# opengarden_v1.net
KiCad netlist of a schematic drawn in EAGLE
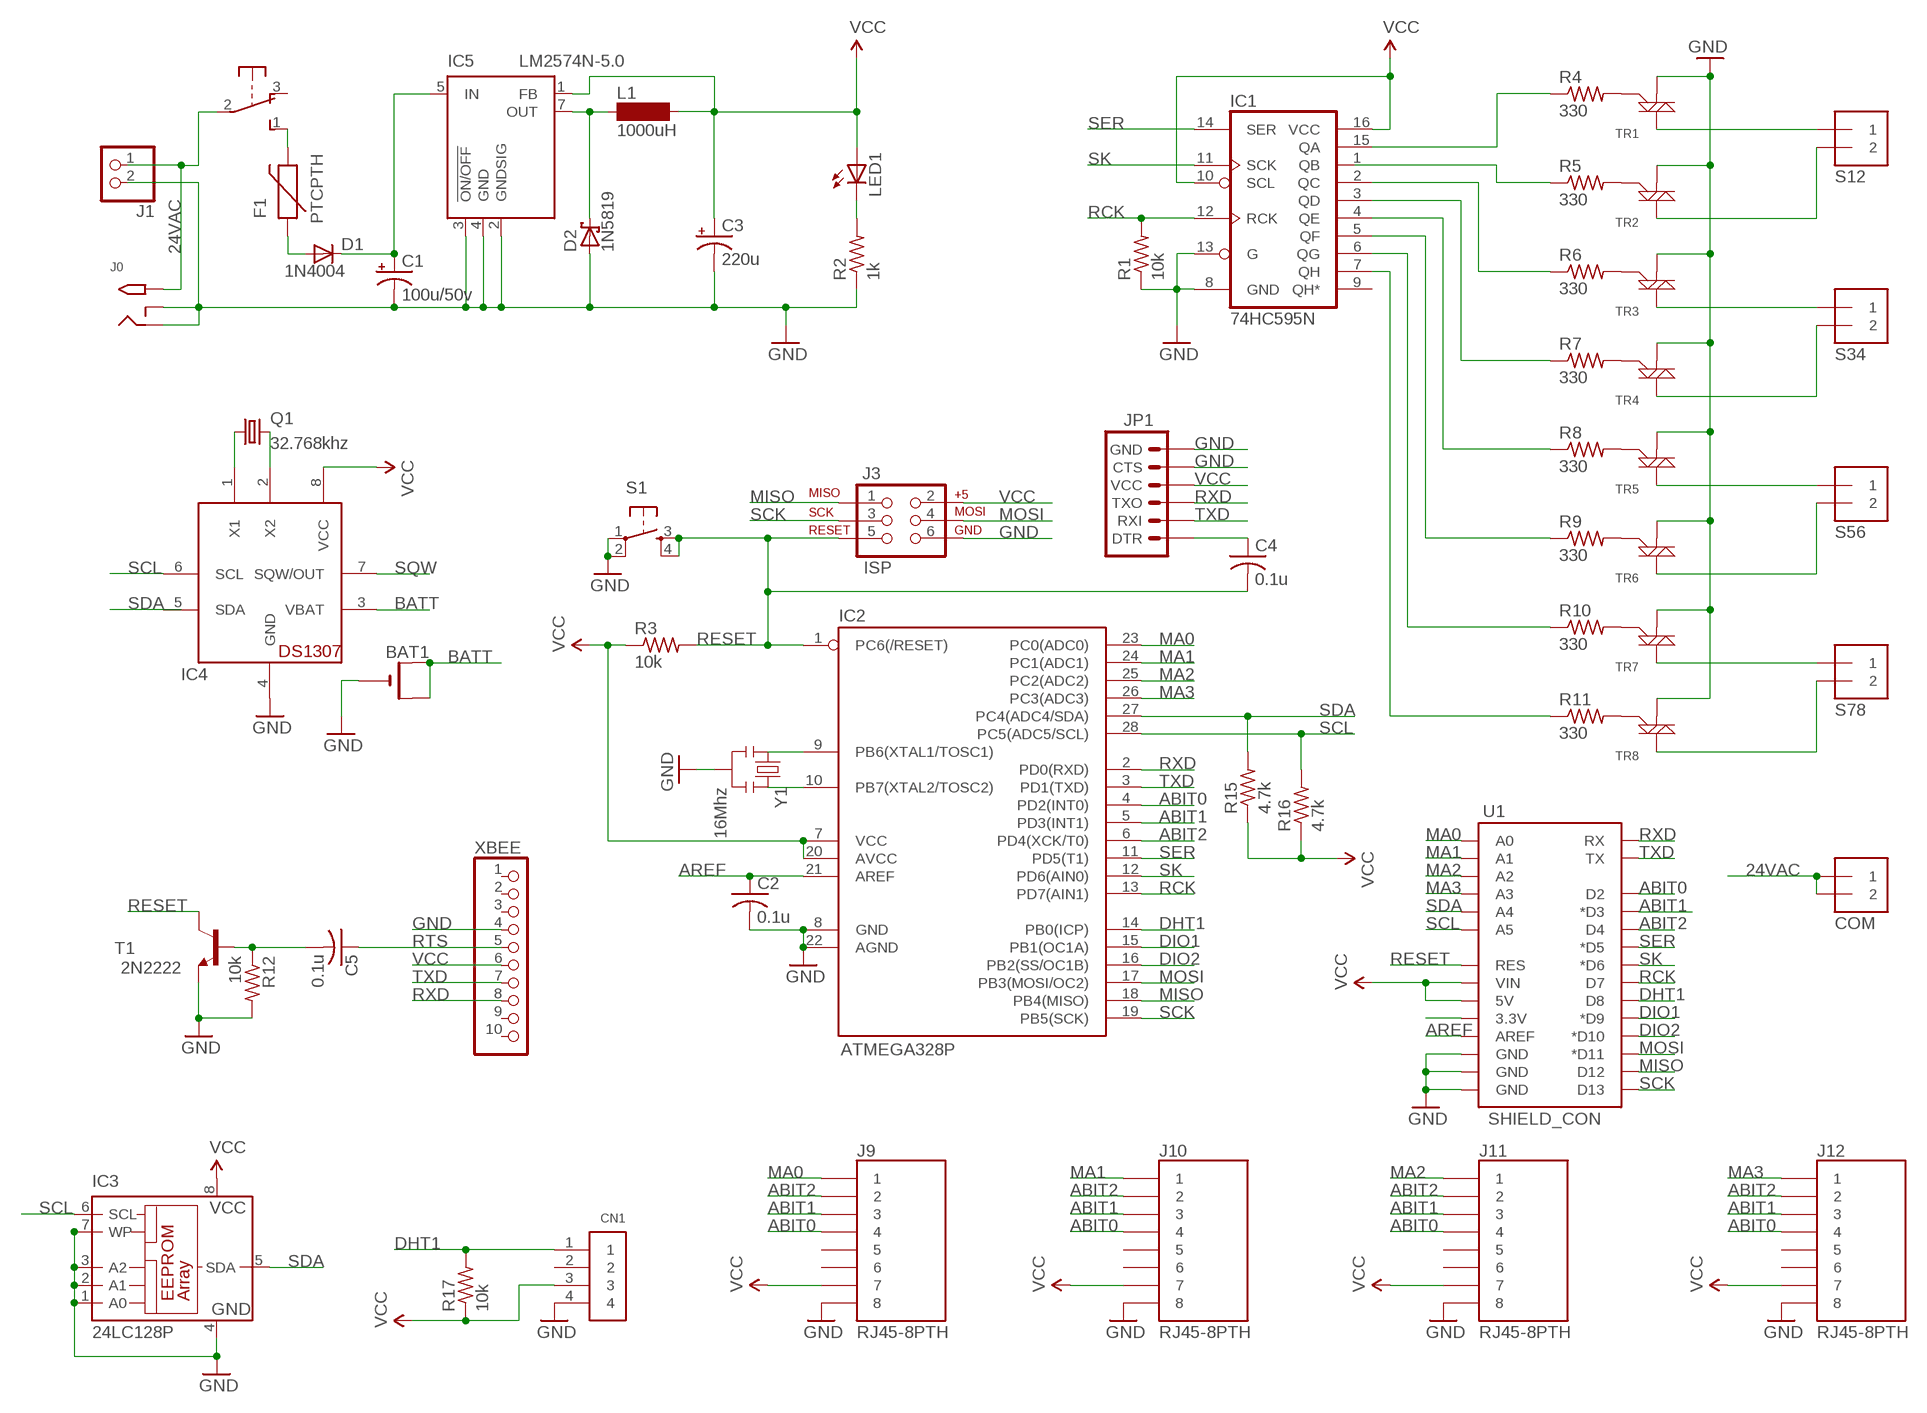
[diagram p0: schematic, sheet 1]

(export (version "E")
  (design (tool "Eeschema 10.0.6"))
  (components
    (comp (ref "BAT1")
      (value "CR1220THM")
      (footprint "eagle-import:CR1220-THM")
      (libsource (lib "eagle-import") (part "CR1220THM"))
    )
    (comp (ref "C1")
      (value "100u/50v")
      (footprint "eagle-import:E3,5-8")
      (libsource (lib "eagle-import") (part "CPOL-USE3.5-8"))
    )
    (comp (ref "C2")
      (value "0.1u")
      (footprint "eagle-import:C025-024X044")
      (libsource (lib "eagle-import") (part "C-US025-024X044"))
    )
    (comp (ref "C3")
      (value "220u")
      (footprint "eagle-import:E2,5-6E")
      (libsource (lib "eagle-import") (part "CPOL-USE2,5-6E"))
    )
    (comp (ref "C4")
      (value "0.1u")
      (footprint "eagle-import:C025-024X044")
      (libsource (lib "eagle-import") (part "C-US025-024X044"))
    )
    (comp (ref "C5")
      (value "0.1u")
      (footprint "eagle-import:C025-024X044")
      (libsource (lib "eagle-import") (part "C-US025-024X044"))
    )
    (comp (ref "CN1")
      (value "1X4-3.5MM")
      (footprint "eagle-import:1X04-3.5MM")
      (libsource (lib "eagle-import") (part "1X4-3.5MM"))
    )
    (comp (ref "COM")
      (value "1X2-3.5MM")
      (footprint "eagle-import:1X2-3.5MM")
      (libsource (lib "eagle-import") (part "1X2-3.5MM"))
    )
    (comp (ref "D1")
      (value "1N4004")
      (footprint "eagle-import:DO41-10")
      (libsource (lib "eagle-import") (part "1N4004"))
    )
    (comp (ref "D2")
      (value "1N5819")
      (footprint "eagle-import:DO41-10")
      (libsource (lib "eagle-import") (part "SCHOTTKY-DIODEDO41"))
    )
    (comp (ref "F1")
      (value "PTCPTH")
      (footprint "eagle-import:PTC")
      (libsource (lib "eagle-import") (part "PTCPTH"))
    )
    (comp (ref "IC1")
      (value "74HC595N")
      (footprint "eagle-import:DIL16")
      (libsource (lib "eagle-import") (part "74595NLS"))
    )
    (comp (ref "IC2")
      (value "ATMEGA328P")
      (footprint "eagle-import:DIL28-3")
      (libsource (lib "eagle-import") (part "AVR-MEGA8-PPTH"))
    )
    (comp (ref "IC3")
      (value "24LC128P")
      (footprint "eagle-import:DIL8")
      (fields (field (name "MF") "MICROCHIP") (field (name "MPN") "24LC128-I/P"))
      (libsource (lib "eagle-import") (part "24PLC128"))
    )
    (comp (ref "IC4")
      (value "DS1307")
      (footprint "eagle-import:DIL08")
      (libsource (lib "eagle-import") (part "DS1307"))
    )
    (comp (ref "IC5")
      (value "LM2574N-5.0")
      (footprint "eagle-import:DIL08")
      (libsource (lib "eagle-import") (part "LM2574?-N5.0"))
    )
    (comp (ref "J0")
      (value "2.1MMJACKTHM")
      (footprint "eagle-import:PJ-102A")
      (libsource (lib "eagle-import") (part "2.1MMJACKTHM"))
    )
    (comp (ref "J1")
      (value "JST_2PIN-THM")
      (footprint "eagle-import:JST-PH-2-THM")
      (libsource (lib "eagle-import") (part "JST_2PIN-THM"))
    )
    (comp (ref "J2")
      (value "OS102011MA1Q")
      (footprint "eagle-import:OS102011MA1Q")
      (libsource (lib "eagle-import") (part "OS102011MA1Q"))
    )
    (comp (ref "J3")
      (value "ISP")
      (footprint "eagle-import:2X3")
      (libsource (lib "eagle-import") (part "AVR_SPI_PRG_6PTH"))
    )
    (comp (ref "J9")
      (value "RJ45-8PTH")
      (footprint "eagle-import:RJ45-8")
      (libsource (lib "eagle-import") (part "RJ45-8PTH"))
    )
    (comp (ref "J10")
      (value "RJ45-8PTH")
      (footprint "eagle-import:RJ45-8")
      (libsource (lib "eagle-import") (part "RJ45-8PTH"))
    )
    (comp (ref "J11")
      (value "RJ45-8PTH")
      (footprint "eagle-import:RJ45-8")
      (libsource (lib "eagle-import") (part "RJ45-8PTH"))
    )
    (comp (ref "J12")
      (value "RJ45-8PTH")
      (footprint "eagle-import:RJ45-8")
      (libsource (lib "eagle-import") (part "RJ45-8PTH"))
    )
    (comp (ref "JP1")
      (value "ARDUINO_SERIAL_PROGRAMLOCK")
      (footprint "eagle-import:1X06_LOCK")
      (libsource (lib "eagle-import") (part "ARDUINO_SERIAL_PROGRAMLOCK"))
    )
    (comp (ref "L1")
      (value "1000uH")
      (footprint "eagle-import:BS11")
      (libsource (lib "eagle-import") (part "BS11"))
    )
    (comp (ref "LED1")
      (value "LED3MM")
      (footprint "eagle-import:LED3MM")
      (libsource (lib "eagle-import") (part "LED3MM"))
    )
    (comp (ref "Q1")
      (value "32.768khz")
      (footprint "eagle-import:TC26V")
      (libsource (lib "eagle-import") (part "CRYSTALTC26V"))
    )
    (comp (ref "R1")
      (value "10k")
      (footprint "eagle-import:0204_7")
      (libsource (lib "eagle-import") (part "R-US_0204/7"))
    )
    (comp (ref "R2")
      (value "1k")
      (footprint "eagle-import:0204_7")
      (libsource (lib "eagle-import") (part "R-US_0204/7"))
    )
    (comp (ref "R3")
      (value "10k")
      (footprint "eagle-import:0204_7")
      (libsource (lib "eagle-import") (part "R-US_0204/7"))
    )
    (comp (ref "R4")
      (value "330")
      (footprint "eagle-import:0204_7")
      (libsource (lib "eagle-import") (part "R-US_0204/7"))
    )
    (comp (ref "R5")
      (value "330")
      (footprint "eagle-import:0204_7")
      (libsource (lib "eagle-import") (part "R-US_0204/7"))
    )
    (comp (ref "R6")
      (value "330")
      (footprint "eagle-import:0204_7")
      (libsource (lib "eagle-import") (part "R-US_0204/7"))
    )
    (comp (ref "R7")
      (value "330")
      (footprint "eagle-import:0204_7")
      (libsource (lib "eagle-import") (part "R-US_0204/7"))
    )
    (comp (ref "R8")
      (value "330")
      (footprint "eagle-import:0204_7")
      (libsource (lib "eagle-import") (part "R-US_0204/7"))
    )
    (comp (ref "R9")
      (value "330")
      (footprint "eagle-import:0204_7")
      (libsource (lib "eagle-import") (part "R-US_0204/7"))
    )
    (comp (ref "R10")
      (value "330")
      (footprint "eagle-import:0204_7")
      (libsource (lib "eagle-import") (part "R-US_0204/7"))
    )
    (comp (ref "R11")
      (value "330")
      (footprint "eagle-import:0204_7")
      (libsource (lib "eagle-import") (part "R-US_0204/7"))
    )
    (comp (ref "R12")
      (value "10k")
      (footprint "eagle-import:0204_7")
      (libsource (lib "eagle-import") (part "R-US_0204/7"))
    )
    (comp (ref "R15")
      (value "4.7k")
      (footprint "eagle-import:0204_7")
      (libsource (lib "eagle-import") (part "R-US_0204/7"))
    )
    (comp (ref "R16")
      (value "4.7k")
      (footprint "eagle-import:0204_7")
      (libsource (lib "eagle-import") (part "R-US_0204/7"))
    )
    (comp (ref "R17")
      (value "10k")
      (footprint "eagle-import:0204_7")
      (libsource (lib "eagle-import") (part "R-US_0204/7"))
    )
    (comp (ref "S1")
      (value "TAC_SWITCHPTH")
      (footprint "eagle-import:TACTILE-PTH")
      (libsource (lib "eagle-import") (part "TAC_SWITCHPTH"))
    )
    (comp (ref "S12")
      (value "1X2-3.5MM")
      (footprint "eagle-import:1X2-3.5MM")
      (libsource (lib "eagle-import") (part "1X2-3.5MM"))
    )
    (comp (ref "S34")
      (value "1X2-3.5MM")
      (footprint "eagle-import:1X2-3.5MM")
      (libsource (lib "eagle-import") (part "1X2-3.5MM"))
    )
    (comp (ref "S56")
      (value "1X2-3.5MM")
      (footprint "eagle-import:1X2-3.5MM")
      (libsource (lib "eagle-import") (part "1X2-3.5MM"))
    )
    (comp (ref "S78")
      (value "1X2-3.5MM")
      (footprint "eagle-import:1X2-3.5MM")
      (libsource (lib "eagle-import") (part "1X2-3.5MM"))
    )
    (comp (ref "T1")
      (value "2N2222")
      (footprint "eagle-import:TO92-EBC-OVAL")
      (libsource (lib "eagle-import") (part "2N2222"))
    )
    (comp (ref "TR1")
      (value "TRIACPTH")
      (footprint "eagle-import:TO-92")
      (libsource (lib "eagle-import") (part "TRIACPTH"))
    )
    (comp (ref "TR2")
      (value "TRIACPTH")
      (footprint "eagle-import:TO-92")
      (libsource (lib "eagle-import") (part "TRIACPTH"))
    )
    (comp (ref "TR3")
      (value "TRIACPTH")
      (footprint "eagle-import:TO-92")
      (libsource (lib "eagle-import") (part "TRIACPTH"))
    )
    (comp (ref "TR4")
      (value "TRIACPTH")
      (footprint "eagle-import:TO-92")
      (libsource (lib "eagle-import") (part "TRIACPTH"))
    )
    (comp (ref "TR5")
      (value "TRIACPTH")
      (footprint "eagle-import:TO-92")
      (libsource (lib "eagle-import") (part "TRIACPTH"))
    )
    (comp (ref "TR6")
      (value "TRIACPTH")
      (footprint "eagle-import:TO-92")
      (libsource (lib "eagle-import") (part "TRIACPTH"))
    )
    (comp (ref "TR7")
      (value "TRIACPTH")
      (footprint "eagle-import:TO-92")
      (libsource (lib "eagle-import") (part "TRIACPTH"))
    )
    (comp (ref "TR8")
      (value "TRIACPTH")
      (footprint "eagle-import:TO-92")
      (libsource (lib "eagle-import") (part "TRIACPTH"))
    )
    (comp (ref "U1")
      (value "SHIELD_CON")
      (footprint "eagle-import:DUEMILANOVE_VIAS")
      (libsource (lib "eagle-import") (part "ARDUINO_SHIELDNO_SILK"))
    )
    (comp (ref "XBEE")
      (value "XBEE")
      (footprint "eagle-import:1X10-BIG")
      (libsource (lib "eagle-import") (part "PINHD-1X10"))
    )
    (comp (ref "Y1")
      (value "16Mhz")
      (footprint "eagle-import:RESONATOR-PTH")
      (libsource (lib "eagle-import") (part "RESONATORPTH"))
    )
  )
  (nets
    (net (code "1") (name "/24VAC") (class "Default")
      (node (ref "COM") (pin "1") (pinfunction "1_1") (pintype "passive"))
      (node (ref "COM") (pin "2") (pinfunction "2_2") (pintype "passive"))
      (node (ref "J0") (pin "TIP") (pinfunction "TIP_TIP") (pintype "bidirectional"))
      (node (ref "J1") (pin "1") (pinfunction "2_1") (pintype "passive"))
      (node (ref "J2") (pin "2") (pinfunction "P_2") (pintype "passive"))
    )
    (net (code "2") (name "/ABIT0") (class "Default")
      (node (ref "IC2") (pin "4") (pinfunction "PD2(INT0)_4") (pintype "bidirectional"))
      (node (ref "J10") (pin "4") (pinfunction "4_4") (pintype "bidirectional"))
      (node (ref "J11") (pin "4") (pinfunction "4_4") (pintype "bidirectional"))
      (node (ref "J12") (pin "4") (pinfunction "4_4") (pintype "bidirectional"))
      (node (ref "J9") (pin "4") (pinfunction "4_4") (pintype "bidirectional"))
      (node (ref "U1") (pin "D2") (pinfunction "D2_D2") (pintype "bidirectional"))
    )
    (net (code "3") (name "/ABIT1") (class "Default")
      (node (ref "IC2") (pin "5") (pinfunction "PD3(INT1)_5") (pintype "bidirectional"))
      (node (ref "J10") (pin "3") (pinfunction "3_3") (pintype "bidirectional"))
      (node (ref "J11") (pin "3") (pinfunction "3_3") (pintype "bidirectional"))
      (node (ref "J12") (pin "3") (pinfunction "3_3") (pintype "bidirectional"))
      (node (ref "J9") (pin "3") (pinfunction "3_3") (pintype "bidirectional"))
      (node (ref "U1") (pin "D3") (pinfunction "*D3_D3") (pintype "bidirectional"))
    )
    (net (code "4") (name "/ABIT2") (class "Default")
      (node (ref "IC2") (pin "6") (pinfunction "PD4(XCK/T0)_6") (pintype "bidirectional"))
      (node (ref "J10") (pin "2") (pinfunction "2_2") (pintype "bidirectional"))
      (node (ref "J11") (pin "2") (pinfunction "2_2") (pintype "bidirectional"))
      (node (ref "J12") (pin "2") (pinfunction "2_2") (pintype "bidirectional"))
      (node (ref "J9") (pin "2") (pinfunction "2_2") (pintype "bidirectional"))
      (node (ref "U1") (pin "D4") (pinfunction "D4_D4") (pintype "bidirectional"))
    )
    (net (code "5") (name "/AREF") (class "Default")
      (node (ref "C2") (pin "1") (pinfunction "1_1") (pintype "passive"))
      (node (ref "IC2") (pin "21") (pinfunction "AREF_21") (pintype "bidirectional"))
      (node (ref "U1") (pin "AREF") (pinfunction "AREF_AREF") (pintype "bidirectional"))
    )
    (net (code "6") (name "/BATT") (class "Default")
      (node (ref "BAT1") (pin "+1") (pinfunction "+_+1") (pintype "passive"))
      (node (ref "BAT1") (pin "+2") (pinfunction "+1_+2") (pintype "passive"))
      (node (ref "IC4") (pin "3") (pinfunction "VBAT_3") (pintype "power_in"))
    )
    (net (code "7") (name "/DHT1") (class "Default")
      (node (ref "CN1") (pin "1") (pinfunction "1_1") (pintype "bidirectional"))
      (node (ref "IC2") (pin "14") (pinfunction "PB0(ICP)_14") (pintype "bidirectional"))
      (node (ref "R17") (pin "2") (pinfunction "2_2") (pintype "passive"))
      (node (ref "U1") (pin "D8") (pinfunction "D8_D8") (pintype "bidirectional"))
    )
    (net (code "8") (name "/DIO1") (class "Default")
      (node (ref "IC2") (pin "15") (pinfunction "PB1(OC1A)_15") (pintype "bidirectional"))
      (node (ref "U1") (pin "D9") (pinfunction "*D9_D9") (pintype "bidirectional"))
    )
    (net (code "9") (name "/DIO2") (class "Default")
      (node (ref "IC2") (pin "16") (pinfunction "PB2(SS/OC1B)_16") (pintype "bidirectional"))
      (node (ref "U1") (pin "D10") (pinfunction "*D10_D10") (pintype "bidirectional"))
    )
    (net (code "10") (name "/MA0") (class "Default")
      (node (ref "IC2") (pin "23") (pinfunction "PC0(ADC0)_23") (pintype "bidirectional"))
      (node (ref "J9") (pin "1") (pinfunction "1_1") (pintype "bidirectional"))
      (node (ref "U1") (pin "A0") (pinfunction "A0_A0") (pintype "bidirectional"))
    )
    (net (code "11") (name "/MA1") (class "Default")
      (node (ref "IC2") (pin "24") (pinfunction "PC1(ADC1)_24") (pintype "bidirectional"))
      (node (ref "J10") (pin "1") (pinfunction "1_1") (pintype "bidirectional"))
      (node (ref "U1") (pin "A1") (pinfunction "A1_A1") (pintype "bidirectional"))
    )
    (net (code "12") (name "/MA2") (class "Default")
      (node (ref "IC2") (pin "25") (pinfunction "PC2(ADC2)_25") (pintype "bidirectional"))
      (node (ref "J11") (pin "1") (pinfunction "1_1") (pintype "bidirectional"))
      (node (ref "U1") (pin "A2") (pinfunction "A2_A2") (pintype "bidirectional"))
    )
    (net (code "13") (name "/MA3") (class "Default")
      (node (ref "IC2") (pin "26") (pinfunction "PC3(ADC3)_26") (pintype "bidirectional"))
      (node (ref "J12") (pin "1") (pinfunction "1_1") (pintype "bidirectional"))
      (node (ref "U1") (pin "A3") (pinfunction "A3_A3") (pintype "bidirectional"))
    )
    (net (code "14") (name "/MISO") (class "Default")
      (node (ref "IC2") (pin "18") (pinfunction "PB4(MISO)_18") (pintype "bidirectional"))
      (node (ref "J3") (pin "1") (pinfunction "1_1") (pintype "passive"))
      (node (ref "U1") (pin "D12") (pinfunction "D12_D12") (pintype "bidirectional"))
    )
    (net (code "15") (name "/MOSI") (class "Default")
      (node (ref "IC2") (pin "17") (pinfunction "PB3(MOSI/OC2)_17") (pintype "bidirectional"))
      (node (ref "J3") (pin "4") (pinfunction "4_4") (pintype "passive"))
      (node (ref "U1") (pin "D11") (pinfunction "*D11_D11") (pintype "bidirectional"))
    )
    (net (code "16") (name "/RCK") (class "Default")
      (node (ref "IC1") (pin "12") (pinfunction "RCK_12") (pintype "input"))
      (node (ref "IC2") (pin "13") (pinfunction "PD7(AIN1)_13") (pintype "bidirectional"))
      (node (ref "R1") (pin "2") (pinfunction "2_2") (pintype "passive"))
      (node (ref "U1") (pin "D7") (pinfunction "D7_D7") (pintype "bidirectional"))
    )
    (net (code "17") (name "/RESET") (class "Default")
      (node (ref "C4") (pin "2") (pinfunction "2_2") (pintype "passive"))
      (node (ref "IC2") (pin "1") (pinfunction "PC6(/RESET)_1") (pintype "bidirectional"))
      (node (ref "J3") (pin "5") (pinfunction "5_5") (pintype "passive"))
      (node (ref "R3") (pin "2") (pinfunction "2_2") (pintype "passive"))
      (node (ref "S1") (pin "3") (pinfunction "3_3") (pintype "passive"))
      (node (ref "S1") (pin "4") (pinfunction "4_4") (pintype "passive"))
      (node (ref "T1") (pin "C") (pinfunction "C_C") (pintype "passive"))
      (node (ref "U1") (pin "RES") (pinfunction "RES_RES") (pintype "bidirectional"))
    )
    (net (code "18") (name "/RTS") (class "Default")
      (node (ref "C5") (pin "1") (pinfunction "1_1") (pintype "passive"))
      (node (ref "XBEE") (pin "5") (pinfunction "5_5") (pintype "passive"))
    )
    (net (code "19") (name "/RXD") (class "Default")
      (node (ref "IC2") (pin "2") (pinfunction "PD0(RXD)_2") (pintype "bidirectional"))
      (node (ref "JP1") (pin "3") (pinfunction "TXO_3") (pintype "passive"))
      (node (ref "U1") (pin "RX") (pinfunction "RX_RX") (pintype "bidirectional"))
      (node (ref "XBEE") (pin "8") (pinfunction "8_8") (pintype "passive"))
    )
    (net (code "20") (name "/SCK") (class "Default")
      (node (ref "IC2") (pin "19") (pinfunction "PB5(SCK)_19") (pintype "bidirectional"))
      (node (ref "J3") (pin "3") (pinfunction "3_3") (pintype "passive"))
      (node (ref "U1") (pin "D13") (pinfunction "D13_D13") (pintype "bidirectional"))
    )
    (net (code "21") (name "/SCL") (class "Default")
      (node (ref "IC2") (pin "28") (pinfunction "PC5(ADC5/SCL)_28") (pintype "bidirectional"))
      (node (ref "IC3") (pin "6") (pinfunction "SCL_6") (pintype "input"))
      (node (ref "IC4") (pin "6") (pinfunction "SCL_6") (pintype "bidirectional"))
      (node (ref "R16") (pin "2") (pinfunction "2_2") (pintype "passive"))
      (node (ref "U1") (pin "A5") (pinfunction "A5_A5") (pintype "bidirectional"))
    )
    (net (code "22") (name "/SDA") (class "Default")
      (node (ref "IC2") (pin "27") (pinfunction "PC4(ADC4/SDA)_27") (pintype "bidirectional"))
      (node (ref "IC3") (pin "5") (pinfunction "SDA_5") (pintype "bidirectional"))
      (node (ref "IC4") (pin "5") (pinfunction "SDA_5") (pintype "bidirectional"))
      (node (ref "R15") (pin "2") (pinfunction "2_2") (pintype "passive"))
      (node (ref "U1") (pin "A4") (pinfunction "A4_A4") (pintype "bidirectional"))
    )
    (net (code "23") (name "/SER") (class "Default")
      (node (ref "IC1") (pin "14") (pinfunction "SER_14") (pintype "input"))
      (node (ref "IC2") (pin "11") (pinfunction "PD5(T1)_11") (pintype "bidirectional"))
      (node (ref "U1") (pin "D5") (pinfunction "*D5_D5") (pintype "bidirectional"))
    )
    (net (code "24") (name "/SK") (class "Default")
      (node (ref "IC1") (pin "11") (pinfunction "SCK_11") (pintype "input"))
      (node (ref "IC2") (pin "12") (pinfunction "PD6(AIN0)_12") (pintype "bidirectional"))
      (node (ref "U1") (pin "D6") (pinfunction "*D6_D6") (pintype "bidirectional"))
    )
    (net (code "25") (name "/SQW") (class "Default")
      (node (ref "IC4") (pin "7") (pinfunction "SQW/OUT_7") (pintype "bidirectional"))
    )
    (net (code "26") (name "/TXD") (class "Default")
      (node (ref "IC2") (pin "3") (pinfunction "PD1(TXD)_3") (pintype "bidirectional"))
      (node (ref "JP1") (pin "2") (pinfunction "RXI_2") (pintype "passive"))
      (node (ref "U1") (pin "TX") (pinfunction "TX_TX") (pintype "bidirectional"))
      (node (ref "XBEE") (pin "7") (pinfunction "7_7") (pintype "passive"))
    )
    (net (code "27") (name "GND") (class "Default")
      (node (ref "BAT1") (pin "-") (pinfunction "-_-") (pintype "passive"))
      (node (ref "C1") (pin "-") (pinfunction "-_-") (pintype "passive"))
      (node (ref "C2") (pin "2") (pinfunction "2_2") (pintype "passive"))
      (node (ref "C3") (pin "-") (pinfunction "-_-") (pintype "passive"))
      (node (ref "CN1") (pin "4") (pinfunction "4_4") (pintype "bidirectional"))
      (node (ref "D2") (pin "A") (pinfunction "A_A") (pintype "passive"))
      (node (ref "IC1") (pin "13") (pinfunction "G_13") (pintype "input"))
      (node (ref "IC1") (pin "8") (pinfunction "GND_8") (pintype "power_in"))
      (node (ref "IC2") (pin "22") (pinfunction "AGND_22") (pintype "bidirectional"))
      (node (ref "IC2") (pin "8") (pinfunction "GND_8") (pintype "bidirectional"))
      (node (ref "IC3") (pin "1") (pinfunction "A0_1") (pintype "input"))
      (node (ref "IC3") (pin "2") (pinfunction "A1_2") (pintype "input"))
      (node (ref "IC3") (pin "3") (pinfunction "A2_3") (pintype "input"))
      (node (ref "IC3") (pin "4") (pinfunction "GND_4") (pintype "power_in"))
      (node (ref "IC3") (pin "7") (pinfunction "WP_7") (pintype "input"))
      (node (ref "IC4") (pin "4") (pinfunction "GND_4") (pintype "power_in"))
      (node (ref "IC5") (pin "2") (pinfunction "GNDSIG_2") (pintype "input"))
      (node (ref "IC5") (pin "3") (pinfunction "~{ON/OFF}_3") (pintype "input"))
      (node (ref "IC5") (pin "4") (pinfunction "GND_4") (pintype "power_in"))
      (node (ref "J0") (pin "RING") (pinfunction "RING_RING") (pintype "bidirectional"))
      (node (ref "J0") (pin "RING_SW") (pinfunction "RING_SW_RING_SW") (pintype "bidirectional"))
      (node (ref "J1") (pin "2") (pinfunction "1_2") (pintype "passive"))
      (node (ref "J10") (pin "8") (pinfunction "8_8") (pintype "bidirectional"))
      (node (ref "J11") (pin "8") (pinfunction "8_8") (pintype "bidirectional"))
      (node (ref "J12") (pin "8") (pinfunction "8_8") (pintype "bidirectional"))
      (node (ref "J3") (pin "6") (pinfunction "6_6") (pintype "passive"))
      (node (ref "J9") (pin "8") (pinfunction "8_8") (pintype "bidirectional"))
      (node (ref "JP1") (pin "5") (pinfunction "CTS_5") (pintype "passive"))
      (node (ref "JP1") (pin "6") (pinfunction "GND_6") (pintype "passive"))
      (node (ref "R1") (pin "1") (pinfunction "1_1") (pintype "passive"))
      (node (ref "R12") (pin "2") (pinfunction "2_2") (pintype "passive"))
      (node (ref "R2") (pin "1") (pinfunction "1_1") (pintype "passive"))
      (node (ref "S1") (pin "1") (pinfunction "1_1") (pintype "passive"))
      (node (ref "S1") (pin "2") (pinfunction "2_2") (pintype "passive"))
      (node (ref "T1") (pin "E") (pinfunction "E_E") (pintype "passive"))
      (node (ref "TR1") (pin "1") (pinfunction "M1_1") (pintype "bidirectional"))
      (node (ref "TR2") (pin "1") (pinfunction "M1_1") (pintype "bidirectional"))
      (node (ref "TR3") (pin "1") (pinfunction "M1_1") (pintype "bidirectional"))
      (node (ref "TR4") (pin "1") (pinfunction "M1_1") (pintype "bidirectional"))
      (node (ref "TR5") (pin "1") (pinfunction "M1_1") (pintype "bidirectional"))
      (node (ref "TR6") (pin "1") (pinfunction "M1_1") (pintype "bidirectional"))
      (node (ref "TR7") (pin "1") (pinfunction "M1_1") (pintype "bidirectional"))
      (node (ref "TR8") (pin "1") (pinfunction "M1_1") (pintype "bidirectional"))
      (node (ref "U1") (pin "GND@0") (pinfunction "GND_GND@0") (pintype "bidirectional"))
      (node (ref "U1") (pin "GND@1") (pinfunction "GND_GND@1") (pintype "bidirectional"))
      (node (ref "U1") (pin "GND@2") (pinfunction "GND_GND@2") (pintype "bidirectional"))
      (node (ref "XBEE") (pin "4") (pinfunction "4_4") (pintype "passive"))
      (node (ref "Y1") (pin "2") (pinfunction "2_2") (pintype "passive"))
    )
    (net (code "28") (name "Net-(C5-Pad2)") (class "Default")
      (node (ref "C5") (pin "2") (pinfunction "2_2") (pintype "passive"))
      (node (ref "R12") (pin "1") (pinfunction "1_1") (pintype "passive"))
      (node (ref "T1") (pin "B") (pinfunction "B_B") (pintype "passive"))
    )
    (net (code "29") (name "Net-(F1-1)") (class "Default")
      (node (ref "D1") (pin "A") (pinfunction "A_A") (pintype "passive"))
      (node (ref "F1") (pin "P$1") (pinfunction "1_P$1") (pintype "bidirectional"))
    )
    (net (code "30") (name "Net-(F1-2)") (class "Default")
      (node (ref "F1") (pin "P$2") (pinfunction "2_P$2") (pintype "bidirectional"))
      (node (ref "J2") (pin "1") (pinfunction "S_1") (pintype "passive"))
    )
    (net (code "31") (name "Net-(IC1-QA)") (class "Default")
      (node (ref "IC1") (pin "15") (pinfunction "QA_15") (pintype "tri_state"))
      (node (ref "R4") (pin "1") (pinfunction "1_1") (pintype "passive"))
    )
    (net (code "32") (name "Net-(IC1-QB)") (class "Default")
      (node (ref "IC1") (pin "1") (pinfunction "QB_1") (pintype "tri_state"))
      (node (ref "R5") (pin "1") (pinfunction "1_1") (pintype "passive"))
    )
    (net (code "33") (name "Net-(IC1-QC)") (class "Default")
      (node (ref "IC1") (pin "2") (pinfunction "QC_2") (pintype "tri_state"))
      (node (ref "R6") (pin "1") (pinfunction "1_1") (pintype "passive"))
    )
    (net (code "34") (name "Net-(IC1-QD)") (class "Default")
      (node (ref "IC1") (pin "3") (pinfunction "QD_3") (pintype "tri_state"))
      (node (ref "R7") (pin "1") (pinfunction "1_1") (pintype "passive"))
    )
    (net (code "35") (name "Net-(IC1-QE)") (class "Default")
      (node (ref "IC1") (pin "4") (pinfunction "QE_4") (pintype "tri_state"))
      (node (ref "R8") (pin "1") (pinfunction "1_1") (pintype "passive"))
    )
    (net (code "36") (name "Net-(IC1-QF)") (class "Default")
      (node (ref "IC1") (pin "5") (pinfunction "QF_5") (pintype "tri_state"))
      (node (ref "R9") (pin "1") (pinfunction "1_1") (pintype "passive"))
    )
    (net (code "37") (name "Net-(IC1-QG)") (class "Default")
      (node (ref "IC1") (pin "6") (pinfunction "QG_6") (pintype "tri_state"))
      (node (ref "R10") (pin "1") (pinfunction "1_1") (pintype "passive"))
    )
    (net (code "38") (name "Net-(IC1-QH)") (class "Default")
      (node (ref "IC1") (pin "7") (pinfunction "QH_7") (pintype "tri_state"))
      (node (ref "R11") (pin "1") (pinfunction "1_1") (pintype "passive"))
    )
    (net (code "39") (name "Net-(IC2-PB6(XTAL1{slash}TOSC1))") (class "Default")
      (node (ref "IC2") (pin "9") (pinfunction "PB6(XTAL1/TOSC1)_9") (pintype "bidirectional"))
      (node (ref "Y1") (pin "1") (pinfunction "1_1") (pintype "passive"))
    )
    (net (code "40") (name "Net-(IC2-PB7(XTAL2{slash}TOSC2))") (class "Default")
      (node (ref "IC2") (pin "10") (pinfunction "PB7(XTAL2/TOSC2)_10") (pintype "bidirectional"))
      (node (ref "Y1") (pin "3") (pinfunction "3_3") (pintype "passive"))
    )
    (net (code "41") (name "Net-(IC4-X1)") (class "Default")
      (node (ref "IC4") (pin "1") (pinfunction "X1_1") (pintype "passive"))
      (node (ref "Q1") (pin "1") (pinfunction "1_1") (pintype "passive"))
    )
    (net (code "42") (name "Net-(IC4-X2)") (class "Default")
      (node (ref "IC4") (pin "2") (pinfunction "X2_2") (pintype "passive"))
      (node (ref "Q1") (pin "2") (pinfunction "2_2") (pintype "passive"))
    )
    (net (code "43") (name "Net-(IC5-IN)") (class "Default")
      (node (ref "C1") (pin "+") (pinfunction "+_+") (pintype "passive"))
      (node (ref "D1") (pin "C") (pinfunction "C_C") (pintype "passive"))
      (node (ref "IC5") (pin "5") (pinfunction "IN_5") (pintype "input"))
    )
    (net (code "44") (name "Net-(IC5-OUT)") (class "Default")
      (node (ref "D2") (pin "C") (pinfunction "C_C") (pintype "passive"))
      (node (ref "IC5") (pin "7") (pinfunction "OUT_7") (pintype "passive"))
      (node (ref "L1") (pin "1") (pinfunction "1_1") (pintype "passive"))
    )
    (net (code "45") (name "Net-(JP1-DTR)") (class "Default")
      (node (ref "C4") (pin "1") (pinfunction "1_1") (pintype "passive"))
      (node (ref "JP1") (pin "1") (pinfunction "DTR_1") (pintype "passive"))
    )
    (net (code "46") (name "Net-(LED1-C)") (class "Default")
      (node (ref "LED1") (pin "K") (pinfunction "C_K") (pintype "passive"))
      (node (ref "R2") (pin "2") (pinfunction "2_2") (pintype "passive"))
    )
    (net (code "47") (name "Net-(TR1-G)") (class "Default")
      (node (ref "R4") (pin "2") (pinfunction "2_2") (pintype "passive"))
      (node (ref "TR1") (pin "2") (pinfunction "G_2") (pintype "bidirectional"))
    )
    (net (code "48") (name "Net-(TR1-M2)") (class "Default")
      (node (ref "S12") (pin "1") (pinfunction "1_1") (pintype "passive"))
      (node (ref "TR1") (pin "3") (pinfunction "M2_3") (pintype "bidirectional"))
    )
    (net (code "49") (name "Net-(TR2-G)") (class "Default")
      (node (ref "R5") (pin "2") (pinfunction "2_2") (pintype "passive"))
      (node (ref "TR2") (pin "2") (pinfunction "G_2") (pintype "bidirectional"))
    )
    (net (code "50") (name "Net-(TR2-M2)") (class "Default")
      (node (ref "S12") (pin "2") (pinfunction "2_2") (pintype "passive"))
      (node (ref "TR2") (pin "3") (pinfunction "M2_3") (pintype "bidirectional"))
    )
    (net (code "51") (name "Net-(TR3-G)") (class "Default")
      (node (ref "R6") (pin "2") (pinfunction "2_2") (pintype "passive"))
      (node (ref "TR3") (pin "2") (pinfunction "G_2") (pintype "bidirectional"))
    )
    (net (code "52") (name "Net-(TR3-M2)") (class "Default")
      (node (ref "S34") (pin "1") (pinfunction "1_1") (pintype "passive"))
      (node (ref "TR3") (pin "3") (pinfunction "M2_3") (pintype "bidirectional"))
    )
    (net (code "53") (name "Net-(TR4-G)") (class "Default")
      (node (ref "R7") (pin "2") (pinfunction "2_2") (pintype "passive"))
      (node (ref "TR4") (pin "2") (pinfunction "G_2") (pintype "bidirectional"))
    )
    (net (code "54") (name "Net-(TR4-M2)") (class "Default")
      (node (ref "S34") (pin "2") (pinfunction "2_2") (pintype "passive"))
      (node (ref "TR4") (pin "3") (pinfunction "M2_3") (pintype "bidirectional"))
    )
    (net (code "55") (name "Net-(TR5-G)") (class "Default")
      (node (ref "R8") (pin "2") (pinfunction "2_2") (pintype "passive"))
      (node (ref "TR5") (pin "2") (pinfunction "G_2") (pintype "bidirectional"))
    )
    (net (code "56") (name "Net-(TR5-M2)") (class "Default")
      (node (ref "S56") (pin "1") (pinfunction "1_1") (pintype "passive"))
      (node (ref "TR5") (pin "3") (pinfunction "M2_3") (pintype "bidirectional"))
    )
    (net (code "57") (name "Net-(TR6-G)") (class "Default")
      (node (ref "R9") (pin "2") (pinfunction "2_2") (pintype "passive"))
      (node (ref "TR6") (pin "2") (pinfunction "G_2") (pintype "bidirectional"))
    )
    (net (code "58") (name "Net-(TR6-M2)") (class "Default")
      (node (ref "S56") (pin "2") (pinfunction "2_2") (pintype "passive"))
      (node (ref "TR6") (pin "3") (pinfunction "M2_3") (pintype "bidirectional"))
    )
    (net (code "59") (name "Net-(TR7-G)") (class "Default")
      (node (ref "R10") (pin "2") (pinfunction "2_2") (pintype "passive"))
      (node (ref "TR7") (pin "2") (pinfunction "G_2") (pintype "bidirectional"))
    )
    (net (code "60") (name "Net-(TR7-M2)") (class "Default")
      (node (ref "S78") (pin "1") (pinfunction "1_1") (pintype "passive"))
      (node (ref "TR7") (pin "3") (pinfunction "M2_3") (pintype "bidirectional"))
    )
    (net (code "61") (name "Net-(TR8-G)") (class "Default")
      (node (ref "R11") (pin "2") (pinfunction "2_2") (pintype "passive"))
      (node (ref "TR8") (pin "2") (pinfunction "G_2") (pintype "bidirectional"))
    )
    (net (code "62") (name "Net-(TR8-M2)") (class "Default")
      (node (ref "S78") (pin "2") (pinfunction "2_2") (pintype "passive"))
      (node (ref "TR8") (pin "3") (pinfunction "M2_3") (pintype "bidirectional"))
    )
    (net (code "63") (name "VCC") (class "Default")
      (node (ref "C3") (pin "+") (pinfunction "+_+") (pintype "passive"))
      (node (ref "CN1") (pin "3") (pinfunction "3_3") (pintype "bidirectional"))
      (node (ref "IC1") (pin "10") (pinfunction "SCL_10") (pintype "input"))
      (node (ref "IC1") (pin "16") (pinfunction "VCC_16") (pintype "power_in"))
      (node (ref "IC2") (pin "20") (pinfunction "AVCC_20") (pintype "bidirectional"))
      (node (ref "IC2") (pin "7") (pinfunction "VCC_7") (pintype "bidirectional"))
      (node (ref "IC3") (pin "8") (pinfunction "VCC_8") (pintype "power_in"))
      (node (ref "IC4") (pin "8") (pinfunction "VCC_8") (pintype "power_in"))
      (node (ref "IC5") (pin "1") (pinfunction "FB_1") (pintype "input"))
      (node (ref "J10") (pin "7") (pinfunction "7_7") (pintype "bidirectional"))
      (node (ref "J11") (pin "7") (pinfunction "7_7") (pintype "bidirectional"))
      (node (ref "J12") (pin "7") (pinfunction "7_7") (pintype "bidirectional"))
      (node (ref "J3") (pin "2") (pinfunction "2_2") (pintype "passive"))
      (node (ref "J9") (pin "7") (pinfunction "7_7") (pintype "bidirectional"))
      (node (ref "JP1") (pin "4") (pinfunction "VCC_4") (pintype "passive"))
      (node (ref "L1") (pin "2") (pinfunction "2_2") (pintype "passive"))
      (node (ref "LED1") (pin "A") (pinfunction "A_A") (pintype "passive"))
      (node (ref "R15") (pin "1") (pinfunction "1_1") (pintype "passive"))
      (node (ref "R16") (pin "1") (pinfunction "1_1") (pintype "passive"))
      (node (ref "R17") (pin "1") (pinfunction "1_1") (pintype "passive"))
      (node (ref "R3") (pin "1") (pinfunction "1_1") (pintype "passive"))
      (node (ref "U1") (pin "5V") (pinfunction "5V_5V") (pintype "bidirectional"))
      (node (ref "U1") (pin "VIN") (pinfunction "VIN_VIN") (pintype "bidirectional"))
      (node (ref "XBEE") (pin "6") (pinfunction "6_6") (pintype "passive"))
    )
    (net (code "64") (name "unconnected-(CN1-Pad2)") (class "Default")
      (node (ref "CN1") (pin "2") (pinfunction "2_2") (pintype "bidirectional"))
    )
    (net (code "65") (name "unconnected-(IC1-QH*-Pad9)") (class "Default")
      (node (ref "IC1") (pin "9") (pinfunction "QH*_9") (pintype "tri_state"))
    )
    (net (code "66") (name "unconnected-(J2A-O-Pad3)") (class "Default")
      (node (ref "J2") (pin "3") (pinfunction "O_3") (pintype "passive"))
    )
    (net (code "67") (name "unconnected-(J9-Pad5)") (class "Default")
      (node (ref "J9") (pin "5") (pinfunction "5_5") (pintype "bidirectional"))
    )
    (net (code "68") (name "unconnected-(J9-Pad6)") (class "Default")
      (node (ref "J9") (pin "6") (pinfunction "6_6") (pintype "bidirectional"))
    )
    (net (code "69") (name "unconnected-(J10-Pad5)") (class "Default")
      (node (ref "J10") (pin "5") (pinfunction "5_5") (pintype "bidirectional"))
    )
    (net (code "70") (name "unconnected-(J10-Pad6)") (class "Default")
      (node (ref "J10") (pin "6") (pinfunction "6_6") (pintype "bidirectional"))
    )
    (net (code "71") (name "unconnected-(J11-Pad5)") (class "Default")
      (node (ref "J11") (pin "5") (pinfunction "5_5") (pintype "bidirectional"))
    )
    (net (code "72") (name "unconnected-(J11-Pad6)") (class "Default")
      (node (ref "J11") (pin "6") (pinfunction "6_6") (pintype "bidirectional"))
    )
    (net (code "73") (name "unconnected-(J12-Pad5)") (class "Default")
      (node (ref "J12") (pin "5") (pinfunction "5_5") (pintype "bidirectional"))
    )
    (net (code "74") (name "unconnected-(J12-Pad6)") (class "Default")
      (node (ref "J12") (pin "6") (pinfunction "6_6") (pintype "bidirectional"))
    )
    (net (code "75") (name "unconnected-(U1-Pad3.3V)") (class "Default")
      (node (ref "U1") (pin "3.3V") (pinfunction "3.3V_3.3V") (pintype "bidirectional"))
    )
    (net (code "76") (name "unconnected-(XBEE-Pad1)") (class "Default")
      (node (ref "XBEE") (pin "1") (pinfunction "1_1") (pintype "passive"))
    )
    (net (code "77") (name "unconnected-(XBEE-Pad2)") (class "Default")
      (node (ref "XBEE") (pin "2") (pinfunction "2_2") (pintype "passive"))
    )
    (net (code "78") (name "unconnected-(XBEE-Pad3)") (class "Default")
      (node (ref "XBEE") (pin "3") (pinfunction "3_3") (pintype "passive"))
    )
    (net (code "79") (name "unconnected-(XBEE-Pad9)") (class "Default")
      (node (ref "XBEE") (pin "9") (pinfunction "9_9") (pintype "passive"))
    )
    (net (code "80") (name "unconnected-(XBEE-Pad10)") (class "Default")
      (node (ref "XBEE") (pin "10") (pinfunction "10_10") (pintype "passive"))
    )
  )
)
